# HS_LED_V1.net
KiCad netlist of a schematic drawn in EAGLE
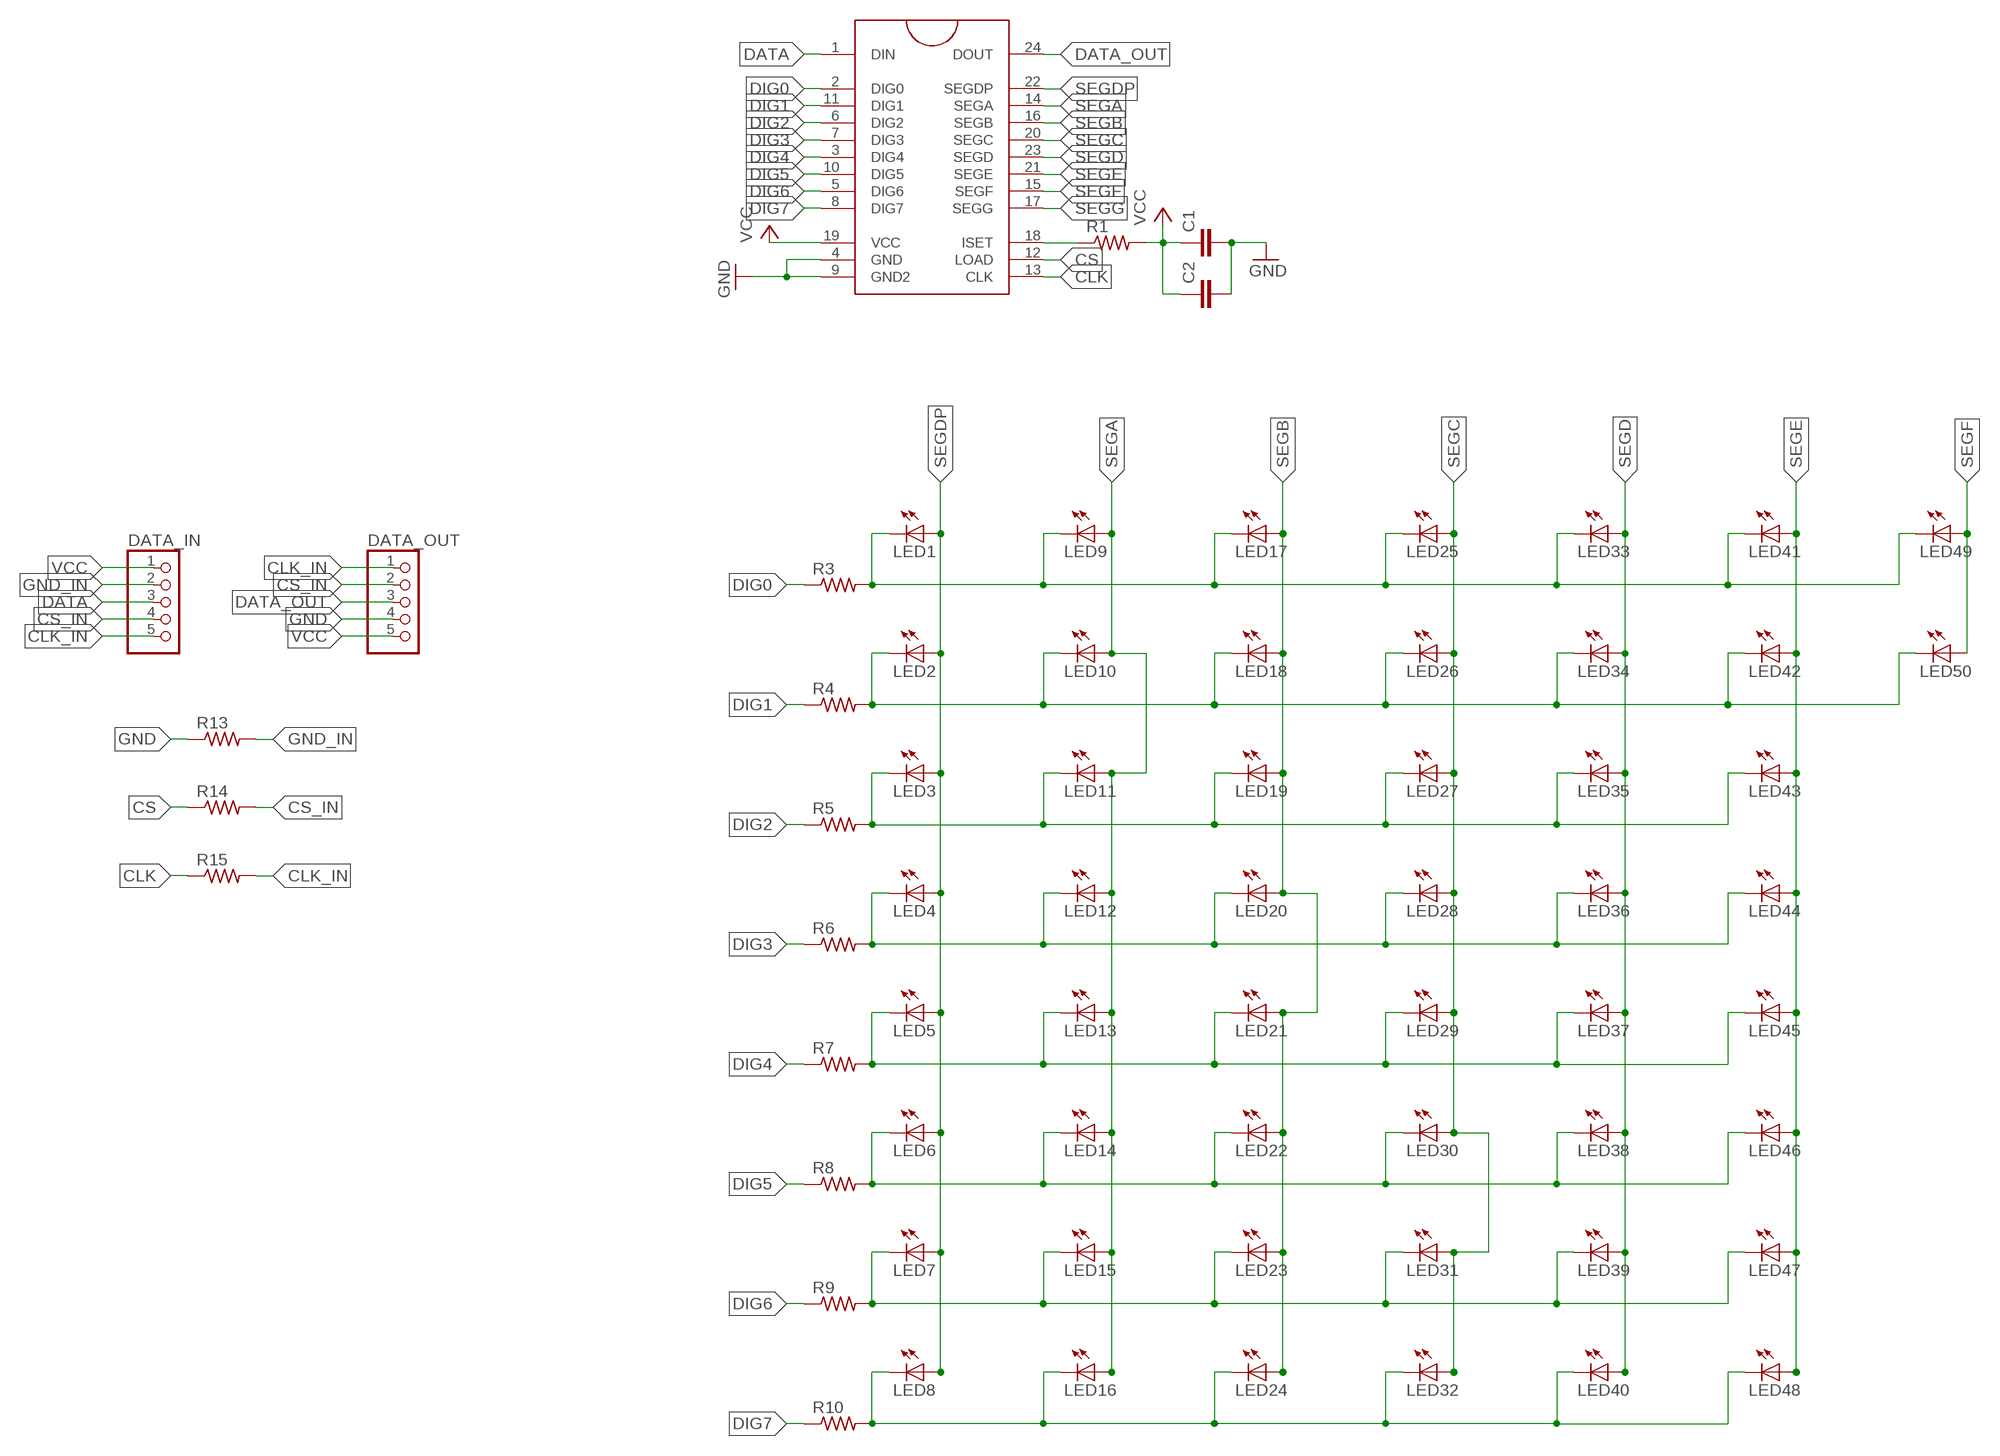
[diagram p0: schematic, sheet 1]

(export (version "E")
  (design (tool "Eeschema 10.0.6"))
  (components
    (comp (ref "C1")
      (value "C-EU025-024X044")
      (footprint "eagle-import:C025-024X044")
      (libsource (lib "eagle-import") (part "C-EU025-024X044"))
    )
    (comp (ref "C2")
      (value "C-EU025-024X044")
      (footprint "eagle-import:C025-024X044")
      (libsource (lib "eagle-import") (part "C-EU025-024X044"))
    )
    (comp (ref "DATA_IN")
      (value "PINHD-1X5/90")
      (footprint "eagle-import:1X05_90")
      (libsource (lib "eagle-import") (part "PINHD-1X5/90"))
    )
    (comp (ref "DATA_OUT")
      (value "PINHD-1X5/90")
      (footprint "eagle-import:1X05_90")
      (libsource (lib "eagle-import") (part "PINHD-1X5/90"))
    )
    (comp (ref "LED1")
      (value "LED3MM")
      (footprint "eagle-import:LED3MM")
      (libsource (lib "eagle-import") (part "LED3MM"))
    )
    (comp (ref "LED2")
      (value "LED3MM")
      (footprint "eagle-import:LED3MM")
      (libsource (lib "eagle-import") (part "LED3MM"))
    )
    (comp (ref "LED3")
      (value "LED3MM")
      (footprint "eagle-import:LED3MM")
      (libsource (lib "eagle-import") (part "LED3MM"))
    )
    (comp (ref "LED4")
      (value "LED3MM")
      (footprint "eagle-import:LED3MM")
      (libsource (lib "eagle-import") (part "LED3MM"))
    )
    (comp (ref "LED5")
      (value "LED3MM")
      (footprint "eagle-import:LED3MM")
      (libsource (lib "eagle-import") (part "LED3MM"))
    )
    (comp (ref "LED6")
      (value "LED3MM")
      (footprint "eagle-import:LED3MM")
      (libsource (lib "eagle-import") (part "LED3MM"))
    )
    (comp (ref "LED7")
      (value "LED3MM")
      (footprint "eagle-import:LED3MM")
      (libsource (lib "eagle-import") (part "LED3MM"))
    )
    (comp (ref "LED8")
      (value "LED3MM")
      (footprint "eagle-import:LED3MM")
      (libsource (lib "eagle-import") (part "LED3MM"))
    )
    (comp (ref "LED9")
      (value "LED3MM")
      (footprint "eagle-import:LED3MM")
      (libsource (lib "eagle-import") (part "LED3MM"))
    )
    (comp (ref "LED10")
      (value "LED3MM")
      (footprint "eagle-import:LED3MM")
      (libsource (lib "eagle-import") (part "LED3MM"))
    )
    (comp (ref "LED11")
      (value "LED3MM")
      (footprint "eagle-import:LED3MM")
      (libsource (lib "eagle-import") (part "LED3MM"))
    )
    (comp (ref "LED12")
      (value "LED3MM")
      (footprint "eagle-import:LED3MM")
      (libsource (lib "eagle-import") (part "LED3MM"))
    )
    (comp (ref "LED13")
      (value "LED3MM")
      (footprint "eagle-import:LED3MM")
      (libsource (lib "eagle-import") (part "LED3MM"))
    )
    (comp (ref "LED14")
      (value "LED3MM")
      (footprint "eagle-import:LED3MM")
      (libsource (lib "eagle-import") (part "LED3MM"))
    )
    (comp (ref "LED15")
      (value "LED3MM")
      (footprint "eagle-import:LED3MM")
      (libsource (lib "eagle-import") (part "LED3MM"))
    )
    (comp (ref "LED16")
      (value "LED3MM")
      (footprint "eagle-import:LED3MM")
      (libsource (lib "eagle-import") (part "LED3MM"))
    )
    (comp (ref "LED17")
      (value "LED3MM")
      (footprint "eagle-import:LED3MM")
      (libsource (lib "eagle-import") (part "LED3MM"))
    )
    (comp (ref "LED18")
      (value "LED3MM")
      (footprint "eagle-import:LED3MM")
      (libsource (lib "eagle-import") (part "LED3MM"))
    )
    (comp (ref "LED19")
      (value "LED3MM")
      (footprint "eagle-import:LED3MM")
      (libsource (lib "eagle-import") (part "LED3MM"))
    )
    (comp (ref "LED20")
      (value "LED3MM")
      (footprint "eagle-import:LED3MM")
      (libsource (lib "eagle-import") (part "LED3MM"))
    )
    (comp (ref "LED21")
      (value "LED3MM")
      (footprint "eagle-import:LED3MM")
      (libsource (lib "eagle-import") (part "LED3MM"))
    )
    (comp (ref "LED22")
      (value "LED3MM")
      (footprint "eagle-import:LED3MM")
      (libsource (lib "eagle-import") (part "LED3MM"))
    )
    (comp (ref "LED23")
      (value "LED3MM")
      (footprint "eagle-import:LED3MM")
      (libsource (lib "eagle-import") (part "LED3MM"))
    )
    (comp (ref "LED24")
      (value "LED3MM")
      (footprint "eagle-import:LED3MM")
      (libsource (lib "eagle-import") (part "LED3MM"))
    )
    (comp (ref "LED25")
      (value "LED3MM")
      (footprint "eagle-import:LED3MM")
      (libsource (lib "eagle-import") (part "LED3MM"))
    )
    (comp (ref "LED26")
      (value "LED3MM")
      (footprint "eagle-import:LED3MM")
      (libsource (lib "eagle-import") (part "LED3MM"))
    )
    (comp (ref "LED27")
      (value "LED3MM")
      (footprint "eagle-import:LED3MM")
      (libsource (lib "eagle-import") (part "LED3MM"))
    )
    (comp (ref "LED28")
      (value "LED3MM")
      (footprint "eagle-import:LED3MM")
      (libsource (lib "eagle-import") (part "LED3MM"))
    )
    (comp (ref "LED29")
      (value "LED3MM")
      (footprint "eagle-import:LED3MM")
      (libsource (lib "eagle-import") (part "LED3MM"))
    )
    (comp (ref "LED30")
      (value "LED3MM")
      (footprint "eagle-import:LED3MM")
      (libsource (lib "eagle-import") (part "LED3MM"))
    )
    (comp (ref "LED31")
      (value "LED3MM")
      (footprint "eagle-import:LED3MM")
      (libsource (lib "eagle-import") (part "LED3MM"))
    )
    (comp (ref "LED32")
      (value "LED3MM")
      (footprint "eagle-import:LED3MM")
      (libsource (lib "eagle-import") (part "LED3MM"))
    )
    (comp (ref "LED33")
      (value "LED3MM")
      (footprint "eagle-import:LED3MM")
      (libsource (lib "eagle-import") (part "LED3MM"))
    )
    (comp (ref "LED34")
      (value "LED3MM")
      (footprint "eagle-import:LED3MM")
      (libsource (lib "eagle-import") (part "LED3MM"))
    )
    (comp (ref "LED35")
      (value "LED3MM")
      (footprint "eagle-import:LED3MM")
      (libsource (lib "eagle-import") (part "LED3MM"))
    )
    (comp (ref "LED36")
      (value "LED3MM")
      (footprint "eagle-import:LED3MM")
      (libsource (lib "eagle-import") (part "LED3MM"))
    )
    (comp (ref "LED37")
      (value "LED3MM")
      (footprint "eagle-import:LED3MM")
      (libsource (lib "eagle-import") (part "LED3MM"))
    )
    (comp (ref "LED38")
      (value "LED3MM")
      (footprint "eagle-import:LED3MM")
      (libsource (lib "eagle-import") (part "LED3MM"))
    )
    (comp (ref "LED39")
      (value "LED3MM")
      (footprint "eagle-import:LED3MM")
      (libsource (lib "eagle-import") (part "LED3MM"))
    )
    (comp (ref "LED40")
      (value "LED3MM")
      (footprint "eagle-import:LED3MM")
      (libsource (lib "eagle-import") (part "LED3MM"))
    )
    (comp (ref "LED41")
      (value "LED3MM")
      (footprint "eagle-import:LED3MM")
      (libsource (lib "eagle-import") (part "LED3MM"))
    )
    (comp (ref "LED42")
      (value "LED3MM")
      (footprint "eagle-import:LED3MM")
      (libsource (lib "eagle-import") (part "LED3MM"))
    )
    (comp (ref "LED43")
      (value "LED3MM")
      (footprint "eagle-import:LED3MM")
      (libsource (lib "eagle-import") (part "LED3MM"))
    )
    (comp (ref "LED44")
      (value "LED3MM")
      (footprint "eagle-import:LED3MM")
      (libsource (lib "eagle-import") (part "LED3MM"))
    )
    (comp (ref "LED45")
      (value "LED3MM")
      (footprint "eagle-import:LED3MM")
      (libsource (lib "eagle-import") (part "LED3MM"))
    )
    (comp (ref "LED46")
      (value "LED3MM")
      (footprint "eagle-import:LED3MM")
      (libsource (lib "eagle-import") (part "LED3MM"))
    )
    (comp (ref "LED47")
      (value "LED3MM")
      (footprint "eagle-import:LED3MM")
      (libsource (lib "eagle-import") (part "LED3MM"))
    )
    (comp (ref "LED48")
      (value "LED3MM")
      (footprint "eagle-import:LED3MM")
      (libsource (lib "eagle-import") (part "LED3MM"))
    )
    (comp (ref "LED49")
      (value "LED3MM")
      (footprint "eagle-import:LED3MM")
      (libsource (lib "eagle-import") (part "LED3MM"))
    )
    (comp (ref "LED50")
      (value "LED3MM")
      (footprint "eagle-import:LED3MM")
      (libsource (lib "eagle-import") (part "LED3MM"))
    )
    (comp (ref "R1")
      (value "R-US_0207/10")
      (footprint "eagle-import:0207_10")
      (libsource (lib "eagle-import") (part "R-US_0207/10"))
    )
    (comp (ref "R3")
      (value "R-US_0207/10")
      (footprint "eagle-import:0207_10")
      (libsource (lib "eagle-import") (part "R-US_0207/10"))
    )
    (comp (ref "R4")
      (value "R-US_0207/10")
      (footprint "eagle-import:0207_10")
      (libsource (lib "eagle-import") (part "R-US_0207/10"))
    )
    (comp (ref "R5")
      (value "R-US_0207/10")
      (footprint "eagle-import:0207_10")
      (libsource (lib "eagle-import") (part "R-US_0207/10"))
    )
    (comp (ref "R6")
      (value "R-US_0207/10")
      (footprint "eagle-import:0207_10")
      (libsource (lib "eagle-import") (part "R-US_0207/10"))
    )
    (comp (ref "R7")
      (value "R-US_0207/10")
      (footprint "eagle-import:0207_10")
      (libsource (lib "eagle-import") (part "R-US_0207/10"))
    )
    (comp (ref "R8")
      (value "R-US_0207/10")
      (footprint "eagle-import:0207_10")
      (libsource (lib "eagle-import") (part "R-US_0207/10"))
    )
    (comp (ref "R9")
      (value "R-US_0207/10")
      (footprint "eagle-import:0207_10")
      (libsource (lib "eagle-import") (part "R-US_0207/10"))
    )
    (comp (ref "R10")
      (value "R-US_0207/10")
      (footprint "eagle-import:0207_10")
      (libsource (lib "eagle-import") (part "R-US_0207/10"))
    )
    (comp (ref "R13")
      (value "R-US_0207/10")
      (footprint "eagle-import:0207_10")
      (libsource (lib "eagle-import") (part "R-US_0207/10"))
    )
    (comp (ref "R14")
      (value "R-US_0207/10")
      (footprint "eagle-import:0207_10")
      (libsource (lib "eagle-import") (part "R-US_0207/10"))
    )
    (comp (ref "R15")
      (value "R-US_0207/10")
      (footprint "eagle-import:0207_10")
      (libsource (lib "eagle-import") (part "R-US_0207/10"))
    )
    (comp (ref "U$1")
      (value "MAX7219DIP")
      (footprint "eagle-import:DIL24")
      (libsource (lib "eagle-import") (part "MAX7219DIP"))
    )
  )
  (nets
    (net (code "1") (name "CLK") (class "Default")
      (node (ref "R15") (pin "1") (pinfunction "1_1") (pintype "passive"))
      (node (ref "U$1") (pin "13") (pinfunction "CLK_13") (pintype "bidirectional"))
    )
    (net (code "2") (name "CLK_IN") (class "Default")
      (node (ref "DATA_IN") (pin "5") (pinfunction "5_5") (pintype "passive"))
      (node (ref "DATA_OUT") (pin "1") (pinfunction "1_1") (pintype "passive"))
      (node (ref "R15") (pin "2") (pinfunction "2_2") (pintype "passive"))
    )
    (net (code "3") (name "CS") (class "Default")
      (node (ref "R14") (pin "1") (pinfunction "1_1") (pintype "passive"))
      (node (ref "U$1") (pin "12") (pinfunction "LOAD_12") (pintype "bidirectional"))
    )
    (net (code "4") (name "CS_IN") (class "Default")
      (node (ref "DATA_IN") (pin "4") (pinfunction "4_4") (pintype "passive"))
      (node (ref "DATA_OUT") (pin "2") (pinfunction "2_2") (pintype "passive"))
      (node (ref "R14") (pin "2") (pinfunction "2_2") (pintype "passive"))
    )
    (net (code "5") (name "DATA") (class "Default")
      (node (ref "DATA_IN") (pin "3") (pinfunction "3_3") (pintype "passive"))
      (node (ref "U$1") (pin "1") (pinfunction "DIN_1") (pintype "bidirectional"))
    )
    (net (code "6") (name "DATA_OUT") (class "Default")
      (node (ref "DATA_OUT") (pin "3") (pinfunction "3_3") (pintype "passive"))
      (node (ref "U$1") (pin "24") (pinfunction "DOUT_24") (pintype "bidirectional"))
    )
    (net (code "7") (name "DIG0") (class "Default")
      (node (ref "R3") (pin "1") (pinfunction "1_1") (pintype "passive"))
      (node (ref "U$1") (pin "2") (pinfunction "DIG0_2") (pintype "bidirectional"))
    )
    (net (code "8") (name "DIG1") (class "Default")
      (node (ref "R4") (pin "1") (pinfunction "1_1") (pintype "passive"))
      (node (ref "U$1") (pin "11") (pinfunction "DIG1_11") (pintype "bidirectional"))
    )
    (net (code "9") (name "DIG2") (class "Default")
      (node (ref "R5") (pin "1") (pinfunction "1_1") (pintype "passive"))
      (node (ref "U$1") (pin "6") (pinfunction "DIG2_6") (pintype "bidirectional"))
    )
    (net (code "10") (name "DIG3") (class "Default")
      (node (ref "R6") (pin "1") (pinfunction "1_1") (pintype "passive"))
      (node (ref "U$1") (pin "7") (pinfunction "DIG3_7") (pintype "bidirectional"))
    )
    (net (code "11") (name "DIG4") (class "Default")
      (node (ref "R7") (pin "1") (pinfunction "1_1") (pintype "passive"))
      (node (ref "U$1") (pin "3") (pinfunction "DIG4_3") (pintype "bidirectional"))
    )
    (net (code "12") (name "DIG5") (class "Default")
      (node (ref "R8") (pin "1") (pinfunction "1_1") (pintype "passive"))
      (node (ref "U$1") (pin "10") (pinfunction "DIG5_10") (pintype "bidirectional"))
    )
    (net (code "13") (name "DIG6") (class "Default")
      (node (ref "R9") (pin "1") (pinfunction "1_1") (pintype "passive"))
      (node (ref "U$1") (pin "5") (pinfunction "DIG6_5") (pintype "bidirectional"))
    )
    (net (code "14") (name "DIG7") (class "Default")
      (node (ref "R10") (pin "1") (pinfunction "1_1") (pintype "passive"))
      (node (ref "U$1") (pin "8") (pinfunction "DIG7_8") (pintype "bidirectional"))
    )
    (net (code "15") (name "GND") (class "Default")
      (node (ref "C1") (pin "2") (pinfunction "2_2") (pintype "passive"))
      (node (ref "C2") (pin "2") (pinfunction "2_2") (pintype "passive"))
      (node (ref "DATA_OUT") (pin "4") (pinfunction "4_4") (pintype "passive"))
      (node (ref "R13") (pin "1") (pinfunction "1_1") (pintype "passive"))
      (node (ref "U$1") (pin "4") (pinfunction "GND_4") (pintype "bidirectional"))
      (node (ref "U$1") (pin "9") (pinfunction "GND2_9") (pintype "bidirectional"))
    )
    (net (code "16") (name "GND_IN") (class "Default")
      (node (ref "DATA_IN") (pin "2") (pinfunction "2_2") (pintype "passive"))
      (node (ref "R13") (pin "2") (pinfunction "2_2") (pintype "passive"))
    )
    (net (code "17") (name "Net-(LED1-C)") (class "Default")
      (node (ref "LED1") (pin "K") (pinfunction "C_K") (pintype "passive"))
      (node (ref "LED17") (pin "K") (pinfunction "C_K") (pintype "passive"))
      (node (ref "LED25") (pin "K") (pinfunction "C_K") (pintype "passive"))
      (node (ref "LED33") (pin "K") (pinfunction "C_K") (pintype "passive"))
      (node (ref "LED41") (pin "K") (pinfunction "C_K") (pintype "passive"))
      (node (ref "LED49") (pin "K") (pinfunction "C_K") (pintype "passive"))
      (node (ref "LED9") (pin "K") (pinfunction "C_K") (pintype "passive"))
      (node (ref "R3") (pin "2") (pinfunction "2_2") (pintype "passive"))
    )
    (net (code "18") (name "Net-(LED10-C)") (class "Default")
      (node (ref "LED10") (pin "K") (pinfunction "C_K") (pintype "passive"))
      (node (ref "LED18") (pin "K") (pinfunction "C_K") (pintype "passive"))
      (node (ref "LED2") (pin "K") (pinfunction "C_K") (pintype "passive"))
      (node (ref "LED26") (pin "K") (pinfunction "C_K") (pintype "passive"))
      (node (ref "LED34") (pin "K") (pinfunction "C_K") (pintype "passive"))
      (node (ref "LED42") (pin "K") (pinfunction "C_K") (pintype "passive"))
      (node (ref "LED50") (pin "K") (pinfunction "C_K") (pintype "passive"))
      (node (ref "R4") (pin "2") (pinfunction "2_2") (pintype "passive"))
    )
    (net (code "19") (name "Net-(LED11-C)") (class "Default")
      (node (ref "LED11") (pin "K") (pinfunction "C_K") (pintype "passive"))
      (node (ref "LED19") (pin "K") (pinfunction "C_K") (pintype "passive"))
      (node (ref "LED27") (pin "K") (pinfunction "C_K") (pintype "passive"))
      (node (ref "LED3") (pin "K") (pinfunction "C_K") (pintype "passive"))
      (node (ref "LED35") (pin "K") (pinfunction "C_K") (pintype "passive"))
      (node (ref "LED43") (pin "K") (pinfunction "C_K") (pintype "passive"))
      (node (ref "R5") (pin "2") (pinfunction "2_2") (pintype "passive"))
    )
    (net (code "20") (name "Net-(LED12-C)") (class "Default")
      (node (ref "LED12") (pin "K") (pinfunction "C_K") (pintype "passive"))
      (node (ref "LED20") (pin "K") (pinfunction "C_K") (pintype "passive"))
      (node (ref "LED28") (pin "K") (pinfunction "C_K") (pintype "passive"))
      (node (ref "LED36") (pin "K") (pinfunction "C_K") (pintype "passive"))
      (node (ref "LED4") (pin "K") (pinfunction "C_K") (pintype "passive"))
      (node (ref "LED44") (pin "K") (pinfunction "C_K") (pintype "passive"))
      (node (ref "R6") (pin "2") (pinfunction "2_2") (pintype "passive"))
    )
    (net (code "21") (name "Net-(LED13-C)") (class "Default")
      (node (ref "LED13") (pin "K") (pinfunction "C_K") (pintype "passive"))
      (node (ref "LED21") (pin "K") (pinfunction "C_K") (pintype "passive"))
      (node (ref "LED29") (pin "K") (pinfunction "C_K") (pintype "passive"))
      (node (ref "LED37") (pin "K") (pinfunction "C_K") (pintype "passive"))
      (node (ref "LED45") (pin "K") (pinfunction "C_K") (pintype "passive"))
      (node (ref "LED5") (pin "K") (pinfunction "C_K") (pintype "passive"))
      (node (ref "R7") (pin "2") (pinfunction "2_2") (pintype "passive"))
    )
    (net (code "22") (name "Net-(LED14-C)") (class "Default")
      (node (ref "LED14") (pin "K") (pinfunction "C_K") (pintype "passive"))
      (node (ref "LED22") (pin "K") (pinfunction "C_K") (pintype "passive"))
      (node (ref "LED30") (pin "K") (pinfunction "C_K") (pintype "passive"))
      (node (ref "LED38") (pin "K") (pinfunction "C_K") (pintype "passive"))
      (node (ref "LED46") (pin "K") (pinfunction "C_K") (pintype "passive"))
      (node (ref "LED6") (pin "K") (pinfunction "C_K") (pintype "passive"))
      (node (ref "R8") (pin "2") (pinfunction "2_2") (pintype "passive"))
    )
    (net (code "23") (name "Net-(LED15-C)") (class "Default")
      (node (ref "LED15") (pin "K") (pinfunction "C_K") (pintype "passive"))
      (node (ref "LED23") (pin "K") (pinfunction "C_K") (pintype "passive"))
      (node (ref "LED31") (pin "K") (pinfunction "C_K") (pintype "passive"))
      (node (ref "LED39") (pin "K") (pinfunction "C_K") (pintype "passive"))
      (node (ref "LED47") (pin "K") (pinfunction "C_K") (pintype "passive"))
      (node (ref "LED7") (pin "K") (pinfunction "C_K") (pintype "passive"))
      (node (ref "R9") (pin "2") (pinfunction "2_2") (pintype "passive"))
    )
    (net (code "24") (name "Net-(LED16-C)") (class "Default")
      (node (ref "LED16") (pin "K") (pinfunction "C_K") (pintype "passive"))
      (node (ref "LED24") (pin "K") (pinfunction "C_K") (pintype "passive"))
      (node (ref "LED32") (pin "K") (pinfunction "C_K") (pintype "passive"))
      (node (ref "LED40") (pin "K") (pinfunction "C_K") (pintype "passive"))
      (node (ref "LED48") (pin "K") (pinfunction "C_K") (pintype "passive"))
      (node (ref "LED8") (pin "K") (pinfunction "C_K") (pintype "passive"))
      (node (ref "R10") (pin "2") (pinfunction "2_2") (pintype "passive"))
    )
    (net (code "25") (name "Net-(U$1-ISET)") (class "Default")
      (node (ref "R1") (pin "1") (pinfunction "1_1") (pintype "passive"))
      (node (ref "U$1") (pin "18") (pinfunction "ISET_18") (pintype "bidirectional"))
    )
    (net (code "26") (name "SEGA") (class "Default")
      (node (ref "LED10") (pin "A") (pinfunction "A_A") (pintype "passive"))
      (node (ref "LED11") (pin "A") (pinfunction "A_A") (pintype "passive"))
      (node (ref "LED12") (pin "A") (pinfunction "A_A") (pintype "passive"))
      (node (ref "LED13") (pin "A") (pinfunction "A_A") (pintype "passive"))
      (node (ref "LED14") (pin "A") (pinfunction "A_A") (pintype "passive"))
      (node (ref "LED15") (pin "A") (pinfunction "A_A") (pintype "passive"))
      (node (ref "LED16") (pin "A") (pinfunction "A_A") (pintype "passive"))
      (node (ref "LED9") (pin "A") (pinfunction "A_A") (pintype "passive"))
      (node (ref "U$1") (pin "14") (pinfunction "SEGA_14") (pintype "bidirectional"))
    )
    (net (code "27") (name "SEGB") (class "Default")
      (node (ref "LED17") (pin "A") (pinfunction "A_A") (pintype "passive"))
      (node (ref "LED18") (pin "A") (pinfunction "A_A") (pintype "passive"))
      (node (ref "LED19") (pin "A") (pinfunction "A_A") (pintype "passive"))
      (node (ref "LED20") (pin "A") (pinfunction "A_A") (pintype "passive"))
      (node (ref "LED21") (pin "A") (pinfunction "A_A") (pintype "passive"))
      (node (ref "LED22") (pin "A") (pinfunction "A_A") (pintype "passive"))
      (node (ref "LED23") (pin "A") (pinfunction "A_A") (pintype "passive"))
      (node (ref "LED24") (pin "A") (pinfunction "A_A") (pintype "passive"))
      (node (ref "U$1") (pin "16") (pinfunction "SEGB_16") (pintype "bidirectional"))
    )
    (net (code "28") (name "SEGC") (class "Default")
      (node (ref "LED25") (pin "A") (pinfunction "A_A") (pintype "passive"))
      (node (ref "LED26") (pin "A") (pinfunction "A_A") (pintype "passive"))
      (node (ref "LED27") (pin "A") (pinfunction "A_A") (pintype "passive"))
      (node (ref "LED28") (pin "A") (pinfunction "A_A") (pintype "passive"))
      (node (ref "LED29") (pin "A") (pinfunction "A_A") (pintype "passive"))
      (node (ref "LED30") (pin "A") (pinfunction "A_A") (pintype "passive"))
      (node (ref "LED31") (pin "A") (pinfunction "A_A") (pintype "passive"))
      (node (ref "LED32") (pin "A") (pinfunction "A_A") (pintype "passive"))
      (node (ref "U$1") (pin "20") (pinfunction "SEGC_20") (pintype "bidirectional"))
    )
    (net (code "29") (name "SEGD") (class "Default")
      (node (ref "LED33") (pin "A") (pinfunction "A_A") (pintype "passive"))
      (node (ref "LED34") (pin "A") (pinfunction "A_A") (pintype "passive"))
      (node (ref "LED35") (pin "A") (pinfunction "A_A") (pintype "passive"))
      (node (ref "LED36") (pin "A") (pinfunction "A_A") (pintype "passive"))
      (node (ref "LED37") (pin "A") (pinfunction "A_A") (pintype "passive"))
      (node (ref "LED38") (pin "A") (pinfunction "A_A") (pintype "passive"))
      (node (ref "LED39") (pin "A") (pinfunction "A_A") (pintype "passive"))
      (node (ref "LED40") (pin "A") (pinfunction "A_A") (pintype "passive"))
      (node (ref "U$1") (pin "23") (pinfunction "SEGD_23") (pintype "bidirectional"))
    )
    (net (code "30") (name "SEGDP") (class "Default")
      (node (ref "LED1") (pin "A") (pinfunction "A_A") (pintype "passive"))
      (node (ref "LED2") (pin "A") (pinfunction "A_A") (pintype "passive"))
      (node (ref "LED3") (pin "A") (pinfunction "A_A") (pintype "passive"))
      (node (ref "LED4") (pin "A") (pinfunction "A_A") (pintype "passive"))
      (node (ref "LED5") (pin "A") (pinfunction "A_A") (pintype "passive"))
      (node (ref "LED6") (pin "A") (pinfunction "A_A") (pintype "passive"))
      (node (ref "LED7") (pin "A") (pinfunction "A_A") (pintype "passive"))
      (node (ref "LED8") (pin "A") (pinfunction "A_A") (pintype "passive"))
      (node (ref "U$1") (pin "22") (pinfunction "SEGDP_22") (pintype "bidirectional"))
    )
    (net (code "31") (name "SEGE") (class "Default")
      (node (ref "LED41") (pin "A") (pinfunction "A_A") (pintype "passive"))
      (node (ref "LED42") (pin "A") (pinfunction "A_A") (pintype "passive"))
      (node (ref "LED43") (pin "A") (pinfunction "A_A") (pintype "passive"))
      (node (ref "LED44") (pin "A") (pinfunction "A_A") (pintype "passive"))
      (node (ref "LED45") (pin "A") (pinfunction "A_A") (pintype "passive"))
      (node (ref "LED46") (pin "A") (pinfunction "A_A") (pintype "passive"))
      (node (ref "LED47") (pin "A") (pinfunction "A_A") (pintype "passive"))
      (node (ref "LED48") (pin "A") (pinfunction "A_A") (pintype "passive"))
      (node (ref "U$1") (pin "21") (pinfunction "SEGE_21") (pintype "bidirectional"))
    )
    (net (code "32") (name "SEGF") (class "Default")
      (node (ref "LED49") (pin "A") (pinfunction "A_A") (pintype "passive"))
      (node (ref "LED50") (pin "A") (pinfunction "A_A") (pintype "passive"))
      (node (ref "U$1") (pin "15") (pinfunction "SEGF_15") (pintype "bidirectional"))
    )
    (net (code "33") (name "SEGG") (class "Default")
      (node (ref "U$1") (pin "17") (pinfunction "SEGG_17") (pintype "bidirectional"))
    )
    (net (code "34") (name "VCC") (class "Default")
      (node (ref "C1") (pin "1") (pinfunction "1_1") (pintype "passive"))
      (node (ref "C2") (pin "1") (pinfunction "1_1") (pintype "passive"))
      (node (ref "DATA_IN") (pin "1") (pinfunction "1_1") (pintype "passive"))
      (node (ref "DATA_OUT") (pin "5") (pinfunction "5_5") (pintype "passive"))
      (node (ref "R1") (pin "2") (pinfunction "2_2") (pintype "passive"))
      (node (ref "U$1") (pin "19") (pinfunction "VCC_19") (pintype "bidirectional"))
    )
  )
)
